# PIC32MX.net
KiCad netlist of a schematic drawn in Altium Designer
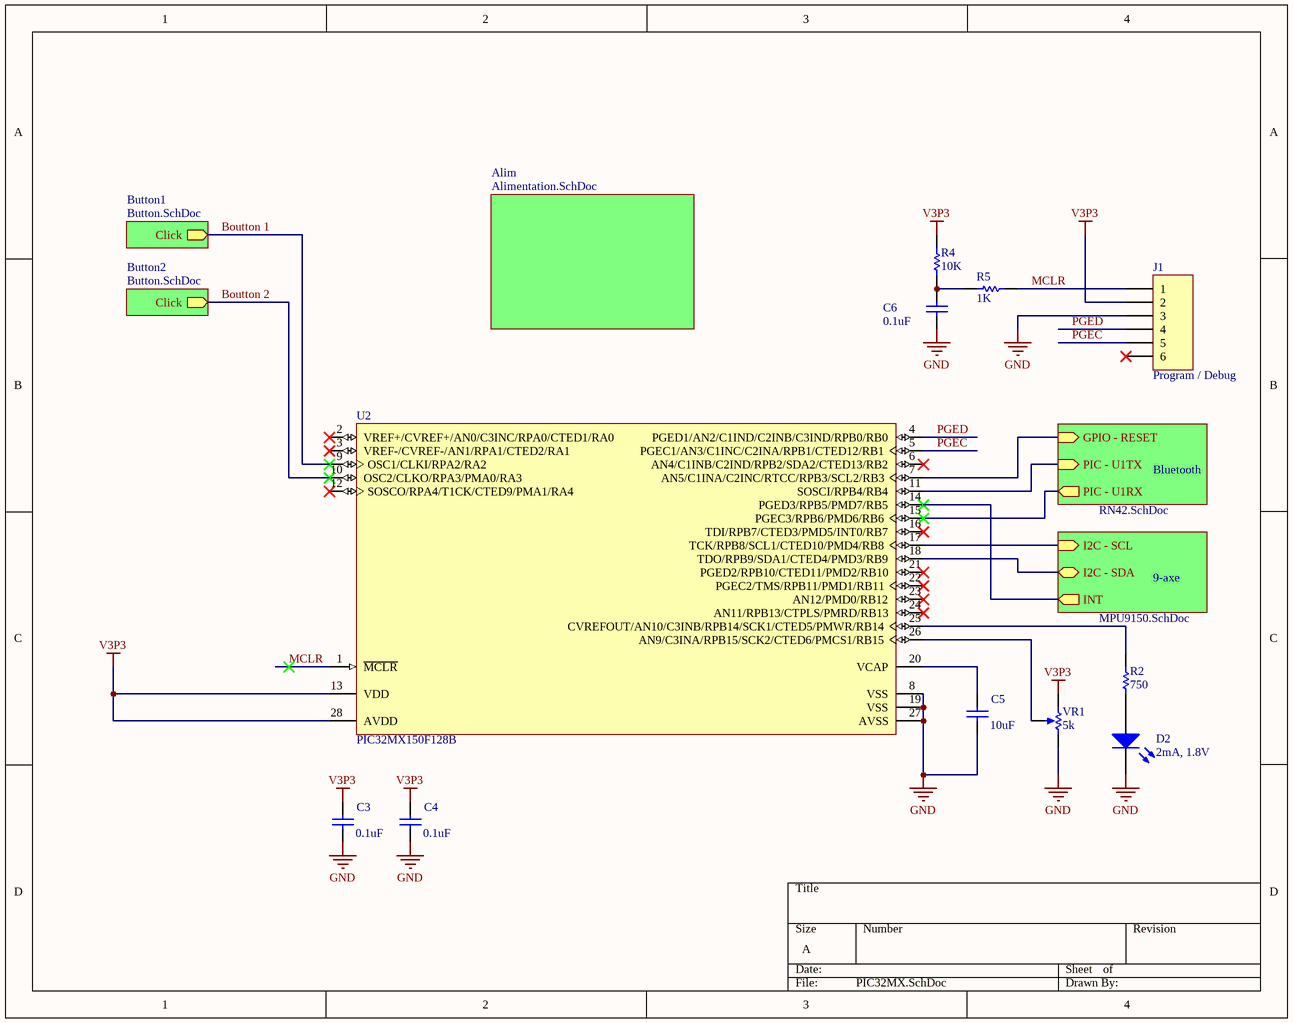
[diagram p0: PIC32MX.SchDoc]

(export (version "E")
  (design (tool "Eeschema 10.0.6"))
  (components
    (comp (ref "C3")
      (value "0.1uF")
      (footprint "CAP 0603")
      (description "Capacitor")
      (libsource (lib "Miscellaneous Devices") (part "Cap"))
    )
    (comp (ref "C4")
      (value "0.1uF")
      (footprint "CAP 0603")
      (description "Capacitor")
      (libsource (lib "Miscellaneous Devices") (part "Cap"))
    )
    (comp (ref "C5")
      (value "10uF")
      (footprint "CAP 0603")
      (description "Capacitor")
      (libsource (lib "Miscellaneous Devices") (part "Cap"))
    )
    (comp (ref "C6")
      (value "0.1uF")
      (footprint "CAP 0603")
      (description "Capacitor")
      (libsource (lib "Miscellaneous Devices") (part "Cap"))
    )
    (comp (ref "D2")
      (value "2mA, 1.8V")
      (footprint "LED")
      (description "Typical INFRARED GaAs LED")
      (libsource (lib "Miscellaneous Devices") (part "LED0"))
    )
    (comp (ref "J1")
      (value "Program / Debug")
      (footprint "ICSP")
      (description "Header, 6-Pin")
      (libsource (lib "Miscellaneous Connectors") (part "MHDR1X6"))
    )
    (comp (ref "R2")
      (value "750")
      (footprint "RES 0603")
      (description "Resistor")
      (libsource (lib "Miscellaneous Devices") (part "Res1"))
    )
    (comp (ref "R4")
      (value "10K")
      (footprint "RES 0603")
      (description "Resistor")
      (libsource (lib "Miscellaneous Devices") (part "Res1"))
    )
    (comp (ref "R5")
      (value "1K")
      (footprint "RES 0603")
      (description "Resistor")
      (libsource (lib "Miscellaneous Devices") (part "Res1"))
    )
    (comp (ref "U2")
      (value "PIC32MX150F128B")
      (footprint "PIC32MX150F128B")
      (description "PIC32MX Family Microcontroller")
      (libsource (lib "Schematics_Library") (part "PIC32MX130F256B"))
    )
    (comp (ref "VR1")
      (value "5k")
      (footprint "91A1A-B28-B13L")
      (description "Potentiometer")
      (libsource (lib "Miscellaneous Devices") (part "RPot"))
    )
  )
  (nets
    (net (code "1") (name "/Boutton 1") (class "Default")
      (node (ref "U2") (pin "9") (pinfunction "OSC1/CLKI/RPA2/RA2_9") (pintype "bidirectional+no_connect"))
    )
    (net (code "2") (name "/Boutton 2") (class "Default")
      (node (ref "U2") (pin "10") (pinfunction "OSC2/CLKO/RPA3/PMA0/RA3_10") (pintype "bidirectional+no_connect"))
    )
    (net (code "3") (name "/GPIO - RESET") (class "Default")
      (node (ref "U2") (pin "7") (pinfunction "AN5/C1INA/C2INC/RTCC/RPB3/SCL2/RB3_7") (pintype "bidirectional"))
    )
    (net (code "4") (name "/I2C - SCL") (class "Default")
      (node (ref "U2") (pin "17") (pinfunction "TCK/RPB8/SCL1/CTED10/PMD4/RB8_17") (pintype "bidirectional"))
    )
    (net (code "5") (name "/I2C - SDA") (class "Default")
      (node (ref "U2") (pin "18") (pinfunction "TDO/RPB9/SDA1/CTED4/PMD3/RB9_18") (pintype "bidirectional"))
    )
    (net (code "6") (name "/INT") (class "Default")
      (node (ref "U2") (pin "14") (pinfunction "PGED3/RPB5/PMD7/RB5_14") (pintype "bidirectional+no_connect"))
    )
    (net (code "7") (name "/MCLR") (class "Default")
      (node (ref "J1") (pin "1") (pinfunction "1_1") (pintype "passive"))
      (node (ref "R5") (pin "1") (pinfunction "1_1") (pintype "passive"))
      (node (ref "U2") (pin "1") (pinfunction "~{MCLR}_1") (pintype "input"))
    )
    (net (code "8") (name "/PGEC") (class "Default")
      (node (ref "J1") (pin "5") (pinfunction "5_5") (pintype "passive"))
      (node (ref "U2") (pin "5") (pinfunction "PGEC1/AN3/C1INC/C2INA/RPB1/CTED12/RB1_5") (pintype "bidirectional"))
    )
    (net (code "9") (name "/PGED") (class "Default")
      (node (ref "J1") (pin "4") (pinfunction "4_4") (pintype "passive"))
      (node (ref "U2") (pin "4") (pinfunction "PGED1/AN2/C1IND/C2INB/C3IND/RPB0/RB0_4") (pintype "bidirectional"))
    )
    (net (code "10") (name "/PIC - U1RX") (class "Default")
      (node (ref "U2") (pin "15") (pinfunction "PGEC3/RPB6/PMD6/RB6_15") (pintype "bidirectional+no_connect"))
    )
    (net (code "11") (name "/PIC - U1TX") (class "Default")
      (node (ref "U2") (pin "11") (pinfunction "SOSCI/RPB4/RB4_11") (pintype "bidirectional"))
    )
    (net (code "12") (name "GND") (class "Default")
      (node (ref "C3") (pin "1") (pinfunction "1_1") (pintype "passive"))
      (node (ref "C4") (pin "1") (pinfunction "1_1") (pintype "passive"))
      (node (ref "C5") (pin "1") (pinfunction "1_1") (pintype "passive"))
      (node (ref "C6") (pin "1") (pinfunction "1_1") (pintype "passive"))
      (node (ref "D2") (pin "2") (pinfunction "K_2") (pintype "passive"))
      (node (ref "J1") (pin "3") (pinfunction "3_3") (pintype "passive"))
      (node (ref "U2") (pin "19") (pinfunction "VSS_19") (pintype "power_in"))
      (node (ref "U2") (pin "27") (pinfunction "AVSS_27") (pintype "power_in"))
      (node (ref "U2") (pin "8") (pinfunction "VSS_8") (pintype "power_in"))
      (node (ref "VR1") (pin "2") (pinfunction "BOT_2") (pintype "passive"))
    )
    (net (code "13") (name "Net-(C6-Pad2)") (class "Default")
      (node (ref "C6") (pin "2") (pinfunction "2_2") (pintype "passive"))
      (node (ref "R4") (pin "1") (pinfunction "1_1") (pintype "passive"))
      (node (ref "R5") (pin "2") (pinfunction "2_2") (pintype "passive"))
    )
    (net (code "14") (name "Net-(D2-A)") (class "Default")
      (node (ref "D2") (pin "1") (pinfunction "A_1") (pintype "passive"))
      (node (ref "R2") (pin "1") (pinfunction "1_1") (pintype "passive"))
    )
    (net (code "15") (name "Net-(U2-AN9{slash}C3INA{slash}RPB15{slash}SCK2{slash}CTED6{slash}PMCS1{slash}RB15)") (class "Default")
      (node (ref "U2") (pin "26") (pinfunction "AN9/C3INA/RPB15/SCK2/CTED6/PMCS1/RB15_26") (pintype "bidirectional"))
      (node (ref "VR1") (pin "3") (pinfunction "TAP_3") (pintype "passive"))
    )
    (net (code "16") (name "Net-(U2-CVREFOUT{slash}AN10{slash}C3INB{slash}RPB14{slash}SCK1{slash}CTED5{slash}PMWR{slash}RB14)") (class "Default")
      (node (ref "R2") (pin "2") (pinfunction "2_2") (pintype "passive"))
      (node (ref "U2") (pin "25") (pinfunction "CVREFOUT/AN10/C3INB/RPB14/SCK1/CTED5/PMWR/RB14_25") (pintype "bidirectional"))
    )
    (net (code "17") (name "Net-(U2-VCAP)") (class "Default")
      (node (ref "C5") (pin "2") (pinfunction "2_2") (pintype "passive"))
      (node (ref "U2") (pin "20") (pinfunction "VCAP_20") (pintype "passive"))
    )
    (net (code "18") (name "V3P3") (class "Default")
      (node (ref "C3") (pin "2") (pinfunction "2_2") (pintype "passive"))
      (node (ref "C4") (pin "2") (pinfunction "2_2") (pintype "passive"))
      (node (ref "J1") (pin "2") (pinfunction "2_2") (pintype "passive"))
      (node (ref "R4") (pin "2") (pinfunction "2_2") (pintype "passive"))
      (node (ref "U2") (pin "13") (pinfunction "VDD_13") (pintype "power_in"))
      (node (ref "U2") (pin "28") (pinfunction "AVDD_28") (pintype "power_in"))
      (node (ref "VR1") (pin "1") (pinfunction "TOP_1") (pintype "passive"))
    )
    (net (code "19") (name "unconnected-(J1-Pad6)") (class "Default")
      (node (ref "J1") (pin "6") (pinfunction "6_6") (pintype "passive+no_connect"))
    )
    (net (code "20") (name "unconnected-(U2-AN4{slash}C1INB{slash}C2IND{slash}RPB2{slash}SDA2{slash}CTED13{slash}RB2-Pad6)") (class "Default")
      (node (ref "U2") (pin "6") (pinfunction "AN4/C1INB/C2IND/RPB2/SDA2/CTED13/RB2_6") (pintype "bidirectional+no_connect"))
    )
    (net (code "21") (name "unconnected-(U2-AN11{slash}RPB13{slash}CTPLS{slash}PMRD{slash}RB13-Pad24)") (class "Default")
      (node (ref "U2") (pin "24") (pinfunction "AN11/RPB13/CTPLS/PMRD/RB13_24") (pintype "bidirectional+no_connect"))
    )
    (net (code "22") (name "unconnected-(U2-AN12{slash}PMD0{slash}RB12-Pad23)") (class "Default")
      (node (ref "U2") (pin "23") (pinfunction "AN12/PMD0/RB12_23") (pintype "bidirectional+no_connect"))
    )
    (net (code "23") (name "unconnected-(U2-PGEC2{slash}TMS{slash}RPB11{slash}PMD1{slash}RB11-Pad22)") (class "Default")
      (node (ref "U2") (pin "22") (pinfunction "PGEC2/TMS/RPB11/PMD1/RB11_22") (pintype "bidirectional+no_connect"))
    )
    (net (code "24") (name "unconnected-(U2-PGED2{slash}RPB10{slash}CTED11{slash}PMD2{slash}RB10-Pad21)") (class "Default")
      (node (ref "U2") (pin "21") (pinfunction "PGED2/RPB10/CTED11/PMD2/RB10_21") (pintype "bidirectional+no_connect"))
    )
    (net (code "25") (name "unconnected-(U2-SOSCO{slash}RPA4{slash}T1CK{slash}CTED9{slash}PMA1{slash}RA4-Pad12)") (class "Default")
      (node (ref "U2") (pin "12") (pinfunction "SOSCO/RPA4/T1CK/CTED9/PMA1/RA4_12") (pintype "bidirectional+no_connect"))
    )
    (net (code "26") (name "unconnected-(U2-TDI{slash}RPB7{slash}CTED3{slash}PMD5{slash}INT0{slash}RB7-Pad16)") (class "Default")
      (node (ref "U2") (pin "16") (pinfunction "TDI/RPB7/CTED3/PMD5/INT0/RB7_16") (pintype "bidirectional+no_connect"))
    )
    (net (code "27") (name "unconnected-(U2-VREF+{slash}CVREF+{slash}AN0{slash}C3INC{slash}RPA0{slash}CTED1{slash}RA0-Pad2)") (class "Default")
      (node (ref "U2") (pin "2") (pinfunction "VREF+/CVREF+/AN0/C3INC/RPA0/CTED1/RA0_2") (pintype "bidirectional+no_connect"))
    )
    (net (code "28") (name "unconnected-(U2-VREF-{slash}CVREF-{slash}AN1{slash}RPA1{slash}CTED2{slash}RA1-Pad3)") (class "Default")
      (node (ref "U2") (pin "3") (pinfunction "VREF-/CVREF-/AN1/RPA1/CTED2/RA1_3") (pintype "bidirectional+no_connect"))
    )
  )
)
